# POR_LICZ-eagle.net
KiCad netlist of a schematic drawn in EAGLE
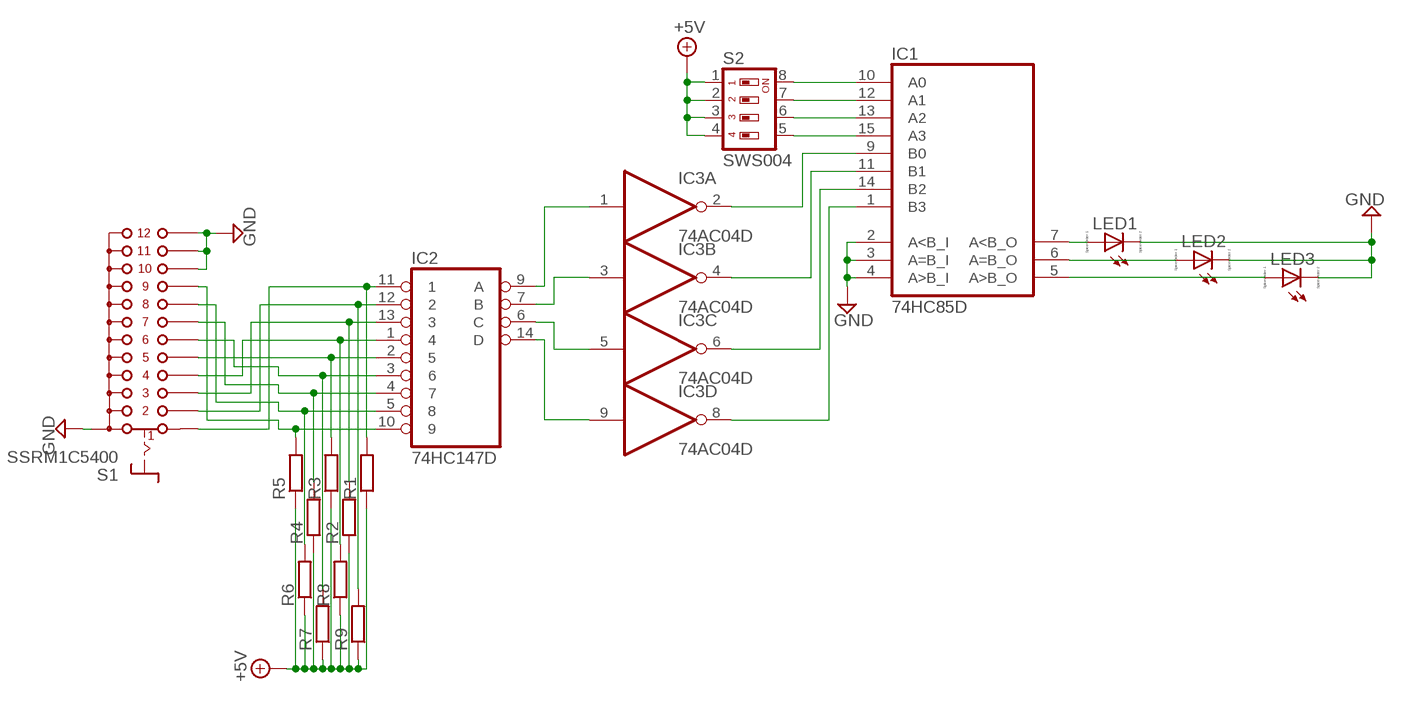
[diagram p0: schematic, sheet 1]

(export (version "E")
  (design (tool "Eeschema 10.0.6"))
  (components
    (comp (ref "IC1")
      (value "74HC85D")
      (footprint "eagle-import:SO16")
      (libsource (lib "eagle-import") (part "7485DHC"))
    )
    (comp (ref "IC2")
      (value "74HC147D")
      (footprint "eagle-import:SO16")
      (libsource (lib "eagle-import") (part "74147DHC"))
    )
    (comp (ref "IC3")
      (value "74AC04D")
      (footprint "eagle-import:SO14")
      (libsource (lib "eagle-import") (part "7404DAC"))
    )
    (comp (ref "LED1")
      (value "LED_E")
      (footprint "eagle-import:LED_1206")
      (libsource (lib "eagle-import") (part "LED_E"))
    )
    (comp (ref "LED2")
      (value "LED_E")
      (footprint "eagle-import:LED_1206")
      (libsource (lib "eagle-import") (part "LED_E"))
    )
    (comp (ref "LED3")
      (value "LED_E")
      (footprint "eagle-import:LED_1206")
      (libsource (lib "eagle-import") (part "LED_E"))
    )
    (comp (ref "R1")
      (value "R-EU_0204/2V")
      (footprint "eagle-import:0204V")
      (libsource (lib "eagle-import") (part "R-EU_0204/2V"))
    )
    (comp (ref "R2")
      (value "R-EU_0204/2V")
      (footprint "eagle-import:0204V")
      (libsource (lib "eagle-import") (part "R-EU_0204/2V"))
    )
    (comp (ref "R3")
      (value "R-EU_0204/2V")
      (footprint "eagle-import:0204V")
      (libsource (lib "eagle-import") (part "R-EU_0204/2V"))
    )
    (comp (ref "R4")
      (value "R-EU_0204/2V")
      (footprint "eagle-import:0204V")
      (libsource (lib "eagle-import") (part "R-EU_0204/2V"))
    )
    (comp (ref "R5")
      (value "R-EU_0204/2V")
      (footprint "eagle-import:0204V")
      (libsource (lib "eagle-import") (part "R-EU_0204/2V"))
    )
    (comp (ref "R6")
      (value "R-EU_0204/2V")
      (footprint "eagle-import:0204V")
      (libsource (lib "eagle-import") (part "R-EU_0204/2V"))
    )
    (comp (ref "R7")
      (value "R-EU_0204/2V")
      (footprint "eagle-import:0204V")
      (libsource (lib "eagle-import") (part "R-EU_0204/2V"))
    )
    (comp (ref "R8")
      (value "R-EU_0204/2V")
      (footprint "eagle-import:0204V")
      (libsource (lib "eagle-import") (part "R-EU_0204/2V"))
    )
    (comp (ref "R9")
      (value "R-EU_0204/2V")
      (footprint "eagle-import:0204V")
      (libsource (lib "eagle-import") (part "R-EU_0204/2V"))
    )
    (comp (ref "S1")
      (value "SSRM1C5400")
      (footprint "eagle-import:SRRM1C5400")
      (libsource (lib "eagle-import") (part "SSRM1C5400"))
    )
    (comp (ref "S2")
      (value "SWS004")
      (footprint "eagle-import:SMS-004")
      (libsource (lib "eagle-import") (part "SWS004"))
    )
  )
  (nets
    (net (code "1") (name "+5V") (class "Default")
      (node (ref "R1") (pin "1") (pinfunction "1_1") (pintype "passive"))
      (node (ref "R2") (pin "1") (pinfunction "1_1") (pintype "passive"))
      (node (ref "R3") (pin "1") (pinfunction "1_1") (pintype "passive"))
      (node (ref "R4") (pin "1") (pinfunction "1_1") (pintype "passive"))
      (node (ref "R5") (pin "1") (pinfunction "1_1") (pintype "passive"))
      (node (ref "R6") (pin "1") (pinfunction "1_1") (pintype "passive"))
      (node (ref "R7") (pin "1") (pinfunction "1_1") (pintype "passive"))
      (node (ref "R8") (pin "1") (pinfunction "1_1") (pintype "passive"))
      (node (ref "R9") (pin "1") (pinfunction "1_1") (pintype "passive"))
      (node (ref "S2") (pin "1") (pinfunction "1_1") (pintype "passive"))
      (node (ref "S2") (pin "2") (pinfunction "2_2") (pintype "passive"))
      (node (ref "S2") (pin "3") (pinfunction "3_3") (pintype "passive"))
      (node (ref "S2") (pin "4") (pinfunction "4_4") (pintype "passive"))
    )
    (net (code "2") (name "GND") (class "Default")
      (node (ref "IC1") (pin "2") (pinfunction "A<B_I_2") (pintype "input"))
      (node (ref "IC1") (pin "3") (pinfunction "A=B_I_3") (pintype "input"))
      (node (ref "IC1") (pin "4") (pinfunction "A>B_I_4") (pintype "input"))
      (node (ref "LED1") (pin "C") (pinfunction "C_C") (pintype "passive"))
      (node (ref "LED2") (pin "C") (pinfunction "C_C") (pintype "passive"))
      (node (ref "LED3") (pin "C") (pinfunction "C_C") (pintype "passive"))
      (node (ref "S1") (pin "10") (pinfunction "10_10") (pintype "passive"))
      (node (ref "S1") (pin "11") (pinfunction "11_11") (pintype "passive"))
      (node (ref "S1") (pin "12") (pinfunction "12_12") (pintype "passive"))
      (node (ref "S1") (pin "13") (pinfunction "A_13") (pintype "passive"))
    )
    (net (code "3") (name "Net-(IC1A-A0)") (class "Default")
      (node (ref "IC1") (pin "10") (pinfunction "A0_10") (pintype "input"))
      (node (ref "S2") (pin "8") (pinfunction "8_8") (pintype "passive"))
    )
    (net (code "4") (name "Net-(IC1A-A1)") (class "Default")
      (node (ref "IC1") (pin "12") (pinfunction "A1_12") (pintype "input"))
      (node (ref "S2") (pin "7") (pinfunction "7_7") (pintype "passive"))
    )
    (net (code "5") (name "Net-(IC1A-A2)") (class "Default")
      (node (ref "IC1") (pin "13") (pinfunction "A2_13") (pintype "input"))
      (node (ref "S2") (pin "6") (pinfunction "6_6") (pintype "passive"))
    )
    (net (code "6") (name "Net-(IC1A-A3)") (class "Default")
      (node (ref "IC1") (pin "15") (pinfunction "A3_15") (pintype "input"))
      (node (ref "S2") (pin "5") (pinfunction "5_5") (pintype "passive"))
    )
    (net (code "7") (name "Net-(IC1A-A<B_O)") (class "Default")
      (node (ref "IC1") (pin "7") (pinfunction "A<B_O_7") (pintype "output"))
      (node (ref "LED1") (pin "A") (pinfunction "A_A") (pintype "passive"))
    )
    (net (code "8") (name "Net-(IC1A-A=B_O)") (class "Default")
      (node (ref "IC1") (pin "6") (pinfunction "A=B_O_6") (pintype "output"))
      (node (ref "LED2") (pin "A") (pinfunction "A_A") (pintype "passive"))
    )
    (net (code "9") (name "Net-(IC1A-A>B_O)") (class "Default")
      (node (ref "IC1") (pin "5") (pinfunction "A>B_O_5") (pintype "output"))
      (node (ref "LED3") (pin "A") (pinfunction "A_A") (pintype "passive"))
    )
    (net (code "10") (name "Net-(IC1A-B0)") (class "Default")
      (node (ref "IC1") (pin "9") (pinfunction "B0_9") (pintype "input"))
      (node (ref "IC3") (pin "2") (pinfunction "O_2") (pintype "output"))
    )
    (net (code "11") (name "Net-(IC1A-B1)") (class "Default")
      (node (ref "IC1") (pin "11") (pinfunction "B1_11") (pintype "input"))
      (node (ref "IC3") (pin "4") (pinfunction "O_4") (pintype "output"))
    )
    (net (code "12") (name "Net-(IC1A-B2)") (class "Default")
      (node (ref "IC1") (pin "14") (pinfunction "B2_14") (pintype "input"))
      (node (ref "IC3") (pin "6") (pinfunction "O_6") (pintype "output"))
    )
    (net (code "13") (name "Net-(IC1A-B3)") (class "Default")
      (node (ref "IC1") (pin "1") (pinfunction "B3_1") (pintype "input"))
      (node (ref "IC3") (pin "8") (pinfunction "O_8") (pintype "output"))
    )
    (net (code "14") (name "Net-(IC2A-1)") (class "Default")
      (node (ref "IC2") (pin "11") (pinfunction "1_11") (pintype "input"))
      (node (ref "R1") (pin "2") (pinfunction "2_2") (pintype "passive"))
      (node (ref "S1") (pin "1") (pinfunction "1_1") (pintype "passive"))
    )
    (net (code "15") (name "Net-(IC2A-2)") (class "Default")
      (node (ref "IC2") (pin "12") (pinfunction "2_12") (pintype "input"))
      (node (ref "R9") (pin "2") (pinfunction "2_2") (pintype "passive"))
      (node (ref "S1") (pin "2") (pinfunction "2_2") (pintype "passive"))
    )
    (net (code "16") (name "Net-(IC2A-3)") (class "Default")
      (node (ref "IC2") (pin "13") (pinfunction "3_13") (pintype "input"))
      (node (ref "R2") (pin "2") (pinfunction "2_2") (pintype "passive"))
      (node (ref "S1") (pin "3") (pinfunction "3_3") (pintype "passive"))
    )
    (net (code "17") (name "Net-(IC2A-4)") (class "Default")
      (node (ref "IC2") (pin "1") (pinfunction "4_1") (pintype "input"))
      (node (ref "R8") (pin "2") (pinfunction "2_2") (pintype "passive"))
      (node (ref "S1") (pin "4") (pinfunction "4_4") (pintype "passive"))
    )
    (net (code "18") (name "Net-(IC2A-5)") (class "Default")
      (node (ref "IC2") (pin "2") (pinfunction "5_2") (pintype "input"))
      (node (ref "R3") (pin "2") (pinfunction "2_2") (pintype "passive"))
      (node (ref "S1") (pin "5") (pinfunction "5_5") (pintype "passive"))
    )
    (net (code "19") (name "Net-(IC2A-6)") (class "Default")
      (node (ref "IC2") (pin "3") (pinfunction "6_3") (pintype "input"))
      (node (ref "R7") (pin "2") (pinfunction "2_2") (pintype "passive"))
      (node (ref "S1") (pin "6") (pinfunction "6_6") (pintype "passive"))
    )
    (net (code "20") (name "Net-(IC2A-7)") (class "Default")
      (node (ref "IC2") (pin "4") (pinfunction "7_4") (pintype "input"))
      (node (ref "R4") (pin "2") (pinfunction "2_2") (pintype "passive"))
      (node (ref "S1") (pin "7") (pinfunction "7_7") (pintype "passive"))
    )
    (net (code "21") (name "Net-(IC2A-8)") (class "Default")
      (node (ref "IC2") (pin "5") (pinfunction "8_5") (pintype "input"))
      (node (ref "R6") (pin "2") (pinfunction "2_2") (pintype "passive"))
      (node (ref "S1") (pin "8") (pinfunction "8_8") (pintype "passive"))
    )
    (net (code "22") (name "Net-(IC2A-9)") (class "Default")
      (node (ref "IC2") (pin "10") (pinfunction "9_10") (pintype "input"))
      (node (ref "R5") (pin "2") (pinfunction "2_2") (pintype "passive"))
      (node (ref "S1") (pin "9") (pinfunction "9_9") (pintype "passive"))
    )
    (net (code "23") (name "Net-(IC2A-A)") (class "Default")
      (node (ref "IC2") (pin "9") (pinfunction "A_9") (pintype "output"))
      (node (ref "IC3") (pin "1") (pinfunction "I_1") (pintype "input"))
    )
    (net (code "24") (name "Net-(IC2A-B)") (class "Default")
      (node (ref "IC2") (pin "7") (pinfunction "B_7") (pintype "output"))
      (node (ref "IC3") (pin "3") (pinfunction "I_3") (pintype "input"))
    )
    (net (code "25") (name "Net-(IC2A-C)") (class "Default")
      (node (ref "IC2") (pin "6") (pinfunction "C_6") (pintype "output"))
      (node (ref "IC3") (pin "5") (pinfunction "I_5") (pintype "input"))
    )
    (net (code "26") (name "Net-(IC2A-D)") (class "Default")
      (node (ref "IC2") (pin "14") (pinfunction "D_14") (pintype "output"))
      (node (ref "IC3") (pin "9") (pinfunction "I_9") (pintype "input"))
    )
  )
)
